# Voicecard-SVF-v05.net
KiCad netlist of a schematic drawn in EAGLE
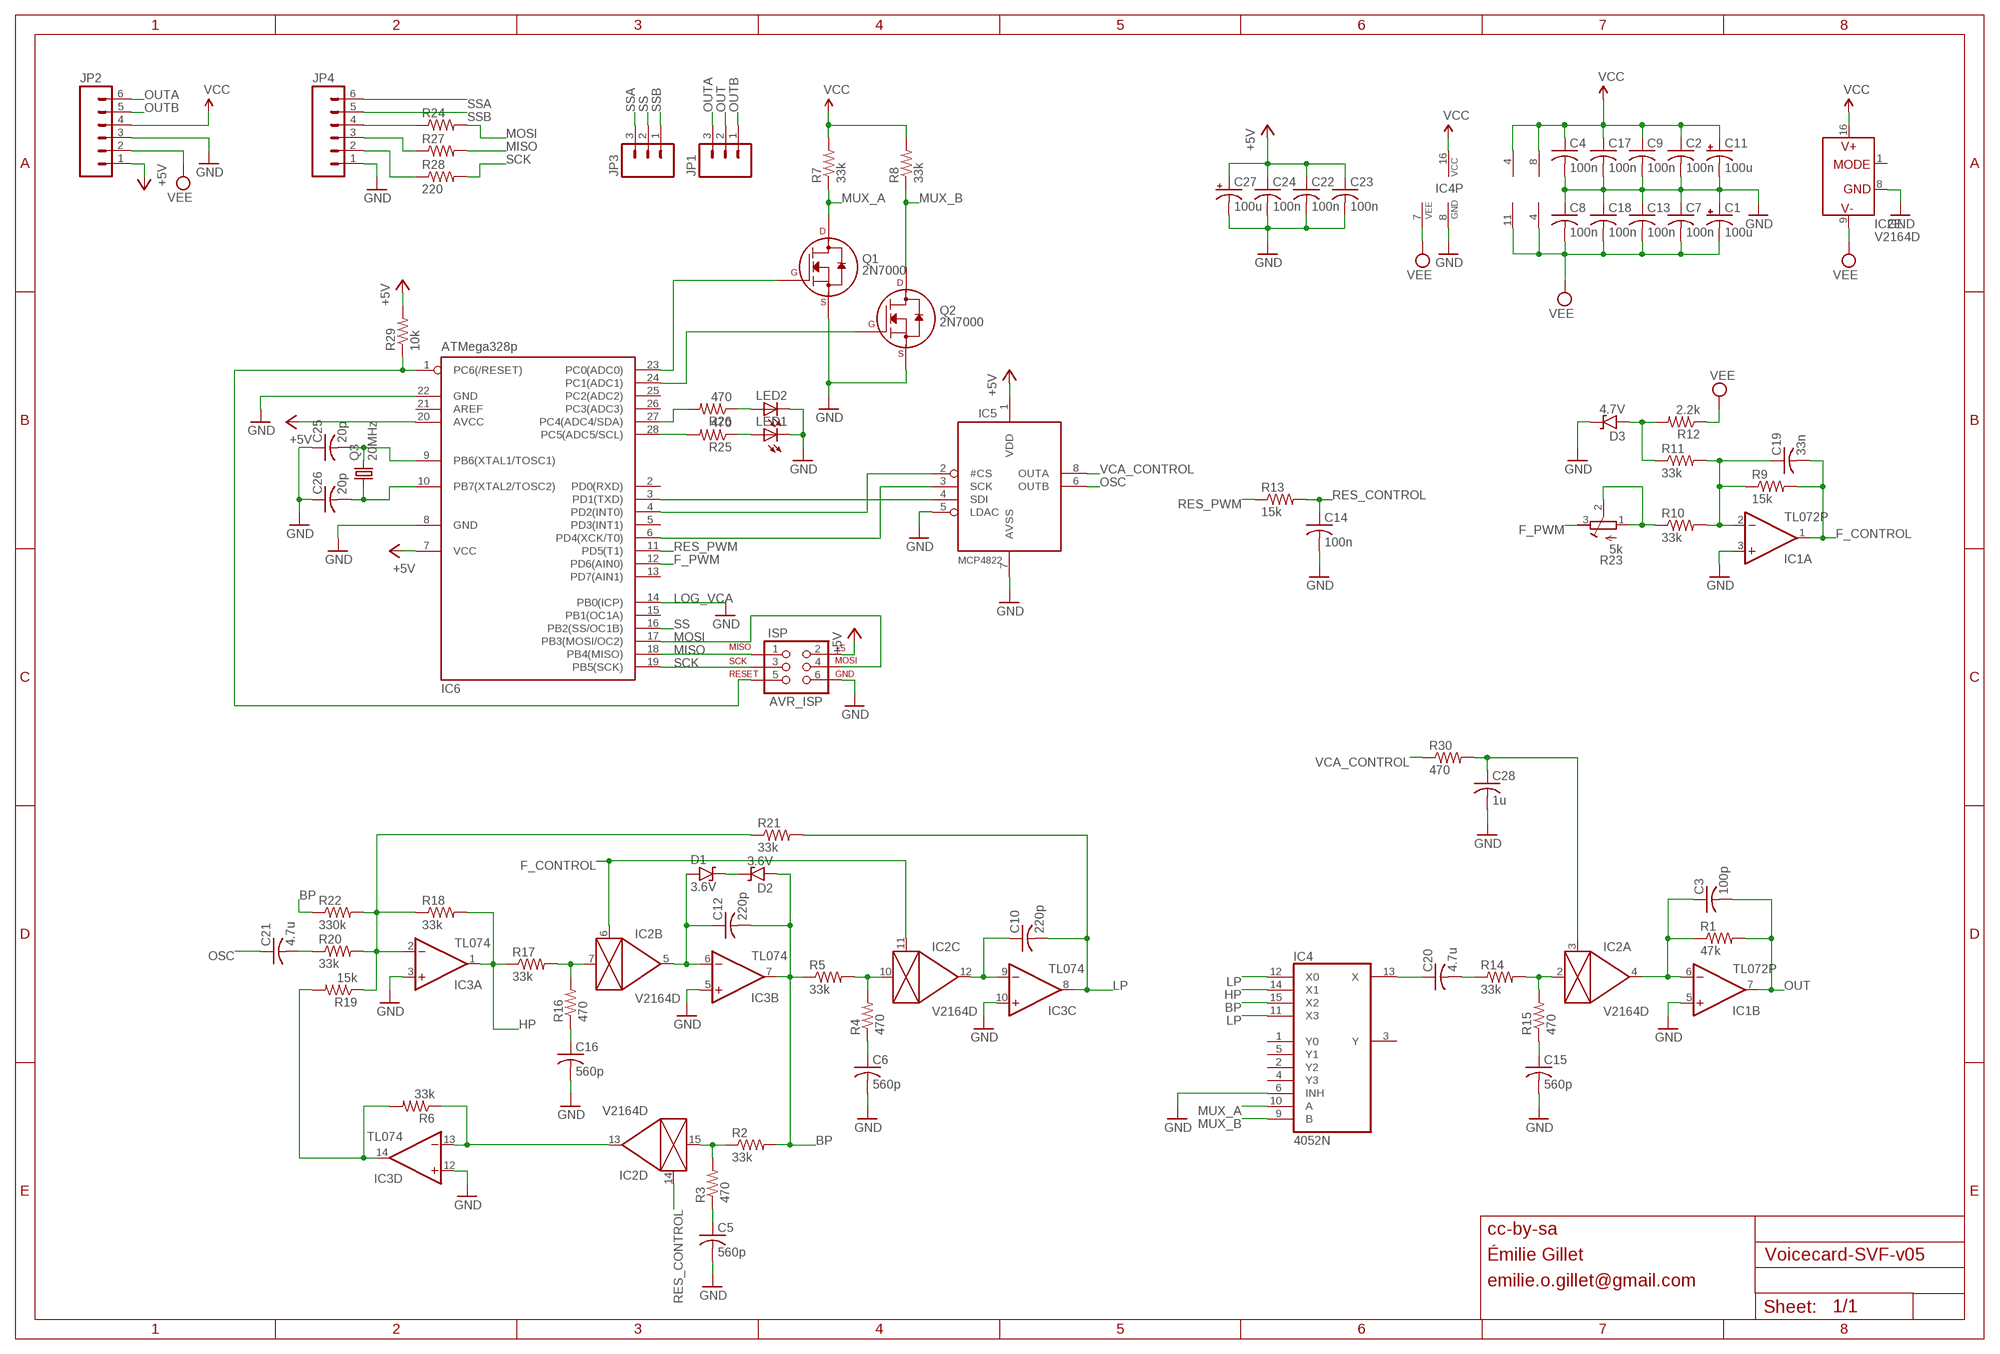
[diagram p0: schematic, sheet 1]

(export (version "E")
  (design (tool "Eeschema 10.0.6"))
  (components
    (comp (ref "C1")
      (value "100u")
      (footprint "eagle-import:E2,5-6")
      (libsource (lib "eagle-import") (part "CPOL-USE2.5-6"))
    )
    (comp (ref "C2")
      (value "100n")
      (footprint "eagle-import:C025-025X050")
      (libsource (lib "eagle-import") (part "C-US025-025X050"))
    )
    (comp (ref "C3")
      (value "100p")
      (footprint "eagle-import:C025-025X050")
      (libsource (lib "eagle-import") (part "C-US025-025X050"))
    )
    (comp (ref "C4")
      (value "100n")
      (footprint "eagle-import:C025-025X050")
      (libsource (lib "eagle-import") (part "C-US025-025X050"))
    )
    (comp (ref "C5")
      (value "560p")
      (footprint "eagle-import:C025-025X050")
      (libsource (lib "eagle-import") (part "C-US025-025X050"))
    )
    (comp (ref "C6")
      (value "560p")
      (footprint "eagle-import:C025-025X050")
      (libsource (lib "eagle-import") (part "C-US025-025X050"))
    )
    (comp (ref "C7")
      (value "100n")
      (footprint "eagle-import:C025-025X050")
      (libsource (lib "eagle-import") (part "C-US025-025X050"))
    )
    (comp (ref "C8")
      (value "100n")
      (footprint "eagle-import:C025-025X050")
      (libsource (lib "eagle-import") (part "C-US025-025X050"))
    )
    (comp (ref "C9")
      (value "100n")
      (footprint "eagle-import:C025-025X050")
      (libsource (lib "eagle-import") (part "C-US025-025X050"))
    )
    (comp (ref "C10")
      (value "220p")
      (footprint "eagle-import:C025-025X050")
      (libsource (lib "eagle-import") (part "C-US025-025X050"))
    )
    (comp (ref "C11")
      (value "100u")
      (footprint "eagle-import:E2,5-6")
      (libsource (lib "eagle-import") (part "CPOL-USE2.5-6"))
    )
    (comp (ref "C12")
      (value "220p")
      (footprint "eagle-import:C025-025X050")
      (libsource (lib "eagle-import") (part "C-US025-025X050"))
    )
    (comp (ref "C13")
      (value "100n")
      (footprint "eagle-import:C025-025X050")
      (libsource (lib "eagle-import") (part "C-US025-025X050"))
    )
    (comp (ref "C14")
      (value "100n")
      (footprint "eagle-import:C025-025X050")
      (libsource (lib "eagle-import") (part "C-US025-025X050"))
    )
    (comp (ref "C15")
      (value "560p")
      (footprint "eagle-import:C025-025X050")
      (libsource (lib "eagle-import") (part "C-US025-025X050"))
    )
    (comp (ref "C16")
      (value "560p")
      (footprint "eagle-import:C025-025X050")
      (libsource (lib "eagle-import") (part "C-US025-025X050"))
    )
    (comp (ref "C17")
      (value "100n")
      (footprint "eagle-import:C025-025X050")
      (libsource (lib "eagle-import") (part "C-US025-025X050"))
    )
    (comp (ref "C18")
      (value "100n")
      (footprint "eagle-import:C025-025X050")
      (libsource (lib "eagle-import") (part "C-US025-025X050"))
    )
    (comp (ref "C19")
      (value "33n")
      (footprint "eagle-import:C050-025X075")
      (libsource (lib "eagle-import") (part "C-US050-025X075"))
    )
    (comp (ref "C20")
      (value "4.7u")
      (footprint "eagle-import:ENP11-6.3")
      (libsource (lib "eagle-import") (part "C-US"))
    )
    (comp (ref "C21")
      (value "4.7u")
      (footprint "eagle-import:ENP11-6.3")
      (libsource (lib "eagle-import") (part "C-US"))
    )
    (comp (ref "C22")
      (value "100n")
      (footprint "eagle-import:C025-025X050")
      (libsource (lib "eagle-import") (part "C-US025-025X050"))
    )
    (comp (ref "C23")
      (value "100n")
      (footprint "eagle-import:C025-025X050")
      (libsource (lib "eagle-import") (part "C-US025-025X050"))
    )
    (comp (ref "C24")
      (value "100n")
      (footprint "eagle-import:C025-024X044")
      (libsource (lib "eagle-import") (part "C-US025-024X044"))
    )
    (comp (ref "C25")
      (value "20p")
      (footprint "eagle-import:C025-024X044")
      (libsource (lib "eagle-import") (part "C-US025-024X044"))
    )
    (comp (ref "C26")
      (value "20p")
      (footprint "eagle-import:C025-024X044")
      (libsource (lib "eagle-import") (part "C-US025-024X044"))
    )
    (comp (ref "C27")
      (value "100u")
      (footprint "eagle-import:E2,5-6")
      (libsource (lib "eagle-import") (part "CPOL-USE2.5-6"))
    )
    (comp (ref "C28")
      (value "1u")
      (footprint "eagle-import:C050-025X075")
      (libsource (lib "eagle-import") (part "C-US050-025X075"))
    )
    (comp (ref "D1")
      (value "3.6V")
      (footprint "eagle-import:D-5")
      (libsource (lib "eagle-import") (part "1N47XXDO35"))
    )
    (comp (ref "D2")
      (value "3.6V")
      (footprint "eagle-import:D-5")
      (libsource (lib "eagle-import") (part "1N47XXDO35"))
    )
    (comp (ref "D3")
      (value "4.7V")
      (footprint "eagle-import:D-5")
      (libsource (lib "eagle-import") (part "1N47XXDO35"))
    )
    (comp (ref "IC1")
      (value "TL072P")
      (footprint "eagle-import:DIL08")
      (libsource (lib "eagle-import") (part "TL072P"))
    )
    (comp (ref "IC2")
      (value "V2164D")
      (footprint "eagle-import:DIL16")
      (libsource (lib "eagle-import") (part "SSM2164P"))
    )
    (comp (ref "IC3")
      (value "TL074")
      (footprint "eagle-import:DIL14")
      (libsource (lib "eagle-import") (part "TL084P"))
    )
    (comp (ref "IC4")
      (value "4052N")
      (footprint "eagle-import:DIL16")
      (libsource (lib "eagle-import") (part "4052N"))
    )
    (comp (ref "IC5")
      (value "MCP4822")
      (footprint "eagle-import:DIL08")
      (libsource (lib "eagle-import") (part "MCP4822"))
    )
    (comp (ref "IC6")
      (value "ATMega328p")
      (footprint "eagle-import:DIL28-3")
      (libsource (lib "eagle-import") (part "MEGA8-P"))
    )
    (comp (ref "ISP")
      (value "AVR_ISP")
      (footprint "eagle-import:2X3")
      (libsource (lib "eagle-import") (part "AVR_SPI_PRG_6PTH"))
    )
    (comp (ref "JP1")
      (value "M03PTH")
      (footprint "eagle-import:1X03")
      (libsource (lib "eagle-import") (part "M03PTH"))
    )
    (comp (ref "JP2")
      (value "M06SIP")
      (footprint "eagle-import:1X06")
      (libsource (lib "eagle-import") (part "M06SIP"))
    )
    (comp (ref "JP3")
      (value "M03PTH")
      (footprint "eagle-import:1X03")
      (libsource (lib "eagle-import") (part "M03PTH"))
    )
    (comp (ref "JP4")
      (value "M06SIP")
      (footprint "eagle-import:1X06")
      (libsource (lib "eagle-import") (part "M06SIP"))
    )
    (comp (ref "LED1")
      (value "LED3MM")
      (footprint "eagle-import:LED3MM")
      (libsource (lib "eagle-import") (part "LED3MM"))
    )
    (comp (ref "LED2")
      (value "LED3MM")
      (footprint "eagle-import:LED3MM")
      (libsource (lib "eagle-import") (part "LED3MM"))
    )
    (comp (ref "Q1")
      (value "2N7000")
      (footprint "eagle-import:TO-92")
      (libsource (lib "eagle-import") (part "2N7000"))
    )
    (comp (ref "Q2")
      (value "2N7000")
      (footprint "eagle-import:TO-92")
      (libsource (lib "eagle-import") (part "2N7000"))
    )
    (comp (ref "Q3")
      (value "20MHz")
      (footprint "eagle-import:HC49U-V")
      (libsource (lib "eagle-import") (part "CRYSTALHC49U-V"))
    )
    (comp (ref "R1")
      (value "47k")
      (footprint "eagle-import:0204_7")
      (libsource (lib "eagle-import") (part "R-US_0204/7"))
    )
    (comp (ref "R2")
      (value "33k")
      (footprint "eagle-import:0204_7")
      (libsource (lib "eagle-import") (part "R-US_0204/7"))
    )
    (comp (ref "R3")
      (value "470")
      (footprint "eagle-import:0204_7")
      (libsource (lib "eagle-import") (part "R-US_0204/7"))
    )
    (comp (ref "R4")
      (value "470")
      (footprint "eagle-import:0204_7")
      (libsource (lib "eagle-import") (part "R-US_0204/7"))
    )
    (comp (ref "R5")
      (value "33k")
      (footprint "eagle-import:0204_7")
      (libsource (lib "eagle-import") (part "R-US_0204/7"))
    )
    (comp (ref "R6")
      (value "33k")
      (footprint "eagle-import:0204_7")
      (libsource (lib "eagle-import") (part "R-US_0204/7"))
    )
    (comp (ref "R7")
      (value "33k")
      (footprint "eagle-import:0204_7")
      (libsource (lib "eagle-import") (part "R-US_0204/7"))
    )
    (comp (ref "R8")
      (value "33k")
      (footprint "eagle-import:0204_7")
      (libsource (lib "eagle-import") (part "R-US_0204/7"))
    )
    (comp (ref "R9")
      (value "15k")
      (footprint "eagle-import:0204_7")
      (libsource (lib "eagle-import") (part "R-US_0204/7"))
    )
    (comp (ref "R10")
      (value "33k")
      (footprint "eagle-import:0204_7")
      (libsource (lib "eagle-import") (part "R-US_0204/7"))
    )
    (comp (ref "R11")
      (value "33k")
      (footprint "eagle-import:0204_7")
      (libsource (lib "eagle-import") (part "R-US_0204/7"))
    )
    (comp (ref "R12")
      (value "2.2k")
      (footprint "eagle-import:0204_7")
      (libsource (lib "eagle-import") (part "R-US_0204/7"))
    )
    (comp (ref "R13")
      (value "15k")
      (footprint "eagle-import:0204_7")
      (libsource (lib "eagle-import") (part "R-US_0204/7"))
    )
    (comp (ref "R14")
      (value "33k")
      (footprint "eagle-import:0204_7")
      (libsource (lib "eagle-import") (part "R-US_0204/7"))
    )
    (comp (ref "R15")
      (value "470")
      (footprint "eagle-import:0204_7")
      (libsource (lib "eagle-import") (part "R-US_0204/7"))
    )
    (comp (ref "R16")
      (value "470")
      (footprint "eagle-import:0204_7")
      (libsource (lib "eagle-import") (part "R-US_0204/7"))
    )
    (comp (ref "R17")
      (value "33k")
      (footprint "eagle-import:0204_7")
      (libsource (lib "eagle-import") (part "R-US_0204/7"))
    )
    (comp (ref "R18")
      (value "33k")
      (footprint "eagle-import:0204_7")
      (libsource (lib "eagle-import") (part "R-US_0204/7"))
    )
    (comp (ref "R19")
      (value "15k")
      (footprint "eagle-import:0204_7")
      (libsource (lib "eagle-import") (part "R-US_0204/7"))
    )
    (comp (ref "R20")
      (value "33k")
      (footprint "eagle-import:0204_7")
      (libsource (lib "eagle-import") (part "R-US_0204/7"))
    )
    (comp (ref "R21")
      (value "33k")
      (footprint "eagle-import:0204_7")
      (libsource (lib "eagle-import") (part "R-US_0204/7"))
    )
    (comp (ref "R22")
      (value "330k")
      (footprint "eagle-import:0204_7")
      (libsource (lib "eagle-import") (part "R-US_0204/7"))
    )
    (comp (ref "R23")
      (value "5k")
      (footprint "eagle-import:RTRIM3296P")
      (libsource (lib "eagle-import") (part "R-TRIMM3296P"))
    )
    (comp (ref "R24")
      (value "220")
      (footprint "eagle-import:0204_7")
      (libsource (lib "eagle-import") (part "R-US_0204/7"))
    )
    (comp (ref "R25")
      (value "470")
      (footprint "eagle-import:0204_7")
      (libsource (lib "eagle-import") (part "R-US_0204/7"))
    )
    (comp (ref "R26")
      (value "470")
      (footprint "eagle-import:0204_7")
      (libsource (lib "eagle-import") (part "R-US_0204/7"))
    )
    (comp (ref "R27")
      (value "220")
      (footprint "eagle-import:0204_7")
      (libsource (lib "eagle-import") (part "R-US_0204/7"))
    )
    (comp (ref "R28")
      (value "220")
      (footprint "eagle-import:0204_7")
      (libsource (lib "eagle-import") (part "R-US_0204/7"))
    )
    (comp (ref "R29")
      (value "10k")
      (footprint "eagle-import:0204_7")
      (libsource (lib "eagle-import") (part "R-US_0204/7"))
    )
    (comp (ref "R30")
      (value "470")
      (footprint "eagle-import:0204_7")
      (libsource (lib "eagle-import") (part "R-US_0204/7"))
    )
  )
  (nets
    (net (code "1") (name "+5V") (class "Default")
      (node (ref "C22") (pin "1") (pinfunction "1_1") (pintype "passive"))
      (node (ref "C23") (pin "1") (pinfunction "1_1") (pintype "passive"))
      (node (ref "C24") (pin "1") (pinfunction "1_1") (pintype "passive"))
      (node (ref "C27") (pin "+") (pinfunction "+_+") (pintype "passive"))
      (node (ref "IC5") (pin "1") (pinfunction "VDD_1") (pintype "power_in"))
      (node (ref "IC6") (pin "20") (pinfunction "AVCC_20") (pintype "power_in"))
      (node (ref "IC6") (pin "7") (pinfunction "VCC_7") (pintype "power_in"))
      (node (ref "ISP") (pin "2") (pinfunction "2_2") (pintype "passive"))
      (node (ref "JP2") (pin "1") (pinfunction "1_1") (pintype "passive"))
      (node (ref "R29") (pin "2") (pinfunction "2_2") (pintype "passive"))
    )
    (net (code "2") (name "/BP") (class "Default")
      (node (ref "C12") (pin "2") (pinfunction "2_2") (pintype "passive"))
      (node (ref "D2") (pin "A") (pinfunction "A_A") (pintype "passive"))
      (node (ref "IC3") (pin "7") (pinfunction "OUT_7") (pintype "output"))
      (node (ref "IC4") (pin "15") (pinfunction "X2_15") (pintype "bidirectional"))
      (node (ref "R2") (pin "2") (pinfunction "2_2") (pintype "passive"))
      (node (ref "R22") (pin "1") (pinfunction "1_1") (pintype "passive"))
      (node (ref "R5") (pin "1") (pinfunction "1_1") (pintype "passive"))
    )
    (net (code "3") (name "/F_CONTROL") (class "Default")
      (node (ref "C19") (pin "2") (pinfunction "2_2") (pintype "passive"))
      (node (ref "IC1") (pin "1") (pinfunction "OUT_1") (pintype "output"))
      (node (ref "IC2") (pin "11") (pinfunction "CTRL_11") (pintype "input"))
      (node (ref "IC2") (pin "6") (pinfunction "CTRL_6") (pintype "input"))
      (node (ref "R9") (pin "2") (pinfunction "2_2") (pintype "passive"))
    )
    (net (code "4") (name "/F_PWM") (class "Default")
      (node (ref "IC6") (pin "12") (pinfunction "PD6(AIN0)_12") (pintype "bidirectional"))
      (node (ref "R23") (pin "3") (pinfunction "A_3") (pintype "passive"))
    )
    (net (code "5") (name "/HP") (class "Default")
      (node (ref "IC3") (pin "1") (pinfunction "OUT_1") (pintype "output"))
      (node (ref "IC4") (pin "14") (pinfunction "X1_14") (pintype "bidirectional"))
      (node (ref "R17") (pin "1") (pinfunction "1_1") (pintype "passive"))
      (node (ref "R18") (pin "2") (pinfunction "2_2") (pintype "passive"))
    )
    (net (code "6") (name "/LP") (class "Default")
      (node (ref "C10") (pin "2") (pinfunction "2_2") (pintype "passive"))
      (node (ref "IC3") (pin "8") (pinfunction "OUT_8") (pintype "output"))
      (node (ref "IC4") (pin "11") (pinfunction "X3_11") (pintype "bidirectional"))
      (node (ref "IC4") (pin "12") (pinfunction "X0_12") (pintype "bidirectional"))
      (node (ref "R21") (pin "2") (pinfunction "2_2") (pintype "passive"))
    )
    (net (code "7") (name "/MISO") (class "Default")
      (node (ref "IC6") (pin "18") (pinfunction "PB4(MISO)_18") (pintype "bidirectional"))
      (node (ref "ISP") (pin "1") (pinfunction "1_1") (pintype "passive"))
      (node (ref "R27") (pin "2") (pinfunction "2_2") (pintype "passive"))
    )
    (net (code "8") (name "/MOSI") (class "Default")
      (node (ref "IC6") (pin "17") (pinfunction "PB3(MOSI/OC2)_17") (pintype "bidirectional"))
      (node (ref "ISP") (pin "4") (pinfunction "4_4") (pintype "passive"))
      (node (ref "R24") (pin "2") (pinfunction "2_2") (pintype "passive"))
    )
    (net (code "9") (name "/MUX_A") (class "Default")
      (node (ref "IC4") (pin "10") (pinfunction "A_10") (pintype "input"))
      (node (ref "Q1") (pin "3") (pinfunction "D_3") (pintype "bidirectional"))
      (node (ref "R7") (pin "1") (pinfunction "1_1") (pintype "passive"))
    )
    (net (code "10") (name "/MUX_B") (class "Default")
      (node (ref "IC4") (pin "9") (pinfunction "B_9") (pintype "input"))
      (node (ref "Q2") (pin "3") (pinfunction "D_3") (pintype "bidirectional"))
      (node (ref "R8") (pin "1") (pinfunction "1_1") (pintype "passive"))
    )
    (net (code "11") (name "/OSC") (class "Default")
      (node (ref "C21") (pin "+") (pinfunction "1_+") (pintype "passive"))
      (node (ref "IC5") (pin "6") (pinfunction "OUTB_6") (pintype "output"))
    )
    (net (code "12") (name "/OUT") (class "Default")
      (node (ref "C3") (pin "2") (pinfunction "2_2") (pintype "passive"))
      (node (ref "IC1") (pin "7") (pinfunction "OUT_7") (pintype "output"))
      (node (ref "JP1") (pin "2") (pinfunction "2_2") (pintype "passive"))
      (node (ref "R1") (pin "2") (pinfunction "2_2") (pintype "passive"))
    )
    (net (code "13") (name "/OUTA") (class "Default")
      (node (ref "JP1") (pin "3") (pinfunction "3_3") (pintype "passive"))
      (node (ref "JP2") (pin "6") (pinfunction "6_6") (pintype "passive"))
    )
    (net (code "14") (name "/OUTB") (class "Default")
      (node (ref "JP1") (pin "1") (pinfunction "1_1") (pintype "passive"))
      (node (ref "JP2") (pin "5") (pinfunction "5_5") (pintype "passive"))
    )
    (net (code "15") (name "/RES_CONTROL") (class "Default")
      (node (ref "C14") (pin "1") (pinfunction "1_1") (pintype "passive"))
      (node (ref "IC2") (pin "14") (pinfunction "CTRL_14") (pintype "input"))
      (node (ref "R13") (pin "2") (pinfunction "2_2") (pintype "passive"))
    )
    (net (code "16") (name "/RES_PWM") (class "Default")
      (node (ref "IC6") (pin "11") (pinfunction "PD5(T1)_11") (pintype "bidirectional"))
      (node (ref "R13") (pin "1") (pinfunction "1_1") (pintype "passive"))
    )
    (net (code "17") (name "/SCK") (class "Default")
      (node (ref "IC6") (pin "19") (pinfunction "PB5(SCK)_19") (pintype "bidirectional"))
      (node (ref "ISP") (pin "3") (pinfunction "3_3") (pintype "passive"))
      (node (ref "R28") (pin "2") (pinfunction "2_2") (pintype "passive"))
    )
    (net (code "18") (name "/SS") (class "Default")
      (node (ref "IC6") (pin "16") (pinfunction "PB2(SS/OC1B)_16") (pintype "bidirectional"))
      (node (ref "JP3") (pin "2") (pinfunction "2_2") (pintype "passive"))
    )
    (net (code "19") (name "/SSA") (class "Default")
      (node (ref "JP3") (pin "3") (pinfunction "3_3") (pintype "passive"))
      (node (ref "JP4") (pin "6") (pinfunction "6_6") (pintype "passive"))
    )
    (net (code "20") (name "/SSB") (class "Default")
      (node (ref "JP3") (pin "1") (pinfunction "1_1") (pintype "passive"))
      (node (ref "JP4") (pin "5") (pinfunction "5_5") (pintype "passive"))
    )
    (net (code "21") (name "/VCA_CONTROL") (class "Default")
      (node (ref "IC5") (pin "8") (pinfunction "OUTA_8") (pintype "output"))
      (node (ref "R30") (pin "1") (pinfunction "1_1") (pintype "passive"))
    )
    (net (code "22") (name "GND") (class "Default")
      (node (ref "C1") (pin "+") (pinfunction "+_+") (pintype "passive"))
      (node (ref "C11") (pin "-") (pinfunction "-_-") (pintype "passive"))
      (node (ref "C13") (pin "1") (pinfunction "1_1") (pintype "passive"))
      (node (ref "C14") (pin "2") (pinfunction "2_2") (pintype "passive"))
      (node (ref "C15") (pin "2") (pinfunction "2_2") (pintype "passive"))
      (node (ref "C16") (pin "2") (pinfunction "2_2") (pintype "passive"))
      (node (ref "C17") (pin "2") (pinfunction "2_2") (pintype "passive"))
      (node (ref "C18") (pin "1") (pinfunction "1_1") (pintype "passive"))
      (node (ref "C2") (pin "2") (pinfunction "2_2") (pintype "passive"))
      (node (ref "C22") (pin "2") (pinfunction "2_2") (pintype "passive"))
      (node (ref "C23") (pin "2") (pinfunction "2_2") (pintype "passive"))
      (node (ref "C24") (pin "2") (pinfunction "2_2") (pintype "passive"))
      (node (ref "C25") (pin "1") (pinfunction "1_1") (pintype "passive"))
      (node (ref "C26") (pin "1") (pinfunction "1_1") (pintype "passive"))
      (node (ref "C27") (pin "-") (pinfunction "-_-") (pintype "passive"))
      (node (ref "C28") (pin "2") (pinfunction "2_2") (pintype "passive"))
      (node (ref "C4") (pin "2") (pinfunction "2_2") (pintype "passive"))
      (node (ref "C5") (pin "2") (pinfunction "2_2") (pintype "passive"))
      (node (ref "C6") (pin "2") (pinfunction "2_2") (pintype "passive"))
      (node (ref "C7") (pin "1") (pinfunction "1_1") (pintype "passive"))
      (node (ref "C8") (pin "1") (pinfunction "1_1") (pintype "passive"))
      (node (ref "C9") (pin "2") (pinfunction "2_2") (pintype "passive"))
      (node (ref "D3") (pin "C") (pinfunction "C_C") (pintype "passive"))
      (node (ref "IC1") (pin "3") (pinfunction "+IN_3") (pintype "input"))
      (node (ref "IC1") (pin "5") (pinfunction "+IN_5") (pintype "input"))
      (node (ref "IC2") (pin "8") (pinfunction "GND_8") (pintype "power_in"))
      (node (ref "IC3") (pin "10") (pinfunction "+IN_10") (pintype "input"))
      (node (ref "IC3") (pin "12") (pinfunction "+IN_12") (pintype "input"))
      (node (ref "IC3") (pin "3") (pinfunction "+IN_3") (pintype "input"))
      (node (ref "IC3") (pin "5") (pinfunction "+IN_5") (pintype "input"))
      (node (ref "IC4") (pin "6") (pinfunction "INH_6") (pintype "input"))
      (node (ref "IC4") (pin "8") (pinfunction "GND_8") (pintype "power_in"))
      (node (ref "IC5") (pin "5") (pinfunction "LDAC_5") (pintype "input"))
      (node (ref "IC5") (pin "7") (pinfunction "AVSS_7") (pintype "power_in"))
      (node (ref "IC6") (pin "14") (pinfunction "PB0(ICP)_14") (pintype "bidirectional"))
      (node (ref "IC6") (pin "22") (pinfunction "GND_22") (pintype "power_in"))
      (node (ref "IC6") (pin "8") (pinfunction "GND_8") (pintype "power_in"))
      (node (ref "ISP") (pin "6") (pinfunction "6_6") (pintype "passive"))
      (node (ref "JP2") (pin "3") (pinfunction "3_3") (pintype "passive"))
      (node (ref "JP4") (pin "1") (pinfunction "1_1") (pintype "passive"))
      (node (ref "LED1") (pin "K") (pinfunction "C_K") (pintype "passive"))
      (node (ref "LED2") (pin "K") (pinfunction "C_K") (pintype "passive"))
      (node (ref "Q1") (pin "1") (pinfunction "S_1") (pintype "bidirectional"))
      (node (ref "Q2") (pin "1") (pinfunction "S_1") (pintype "bidirectional"))
    )
    (net (code "23") (name "Net-(C5-Pad1)") (class "Default")
      (node (ref "C5") (pin "1") (pinfunction "1_1") (pintype "passive"))
      (node (ref "R3") (pin "1") (pinfunction "1_1") (pintype "passive"))
    )
    (net (code "24") (name "Net-(C6-Pad1)") (class "Default")
      (node (ref "C6") (pin "1") (pinfunction "1_1") (pintype "passive"))
      (node (ref "R4") (pin "1") (pinfunction "1_1") (pintype "passive"))
    )
    (net (code "25") (name "Net-(C15-Pad1)") (class "Default")
      (node (ref "C15") (pin "1") (pinfunction "1_1") (pintype "passive"))
      (node (ref "R15") (pin "1") (pinfunction "1_1") (pintype "passive"))
    )
    (net (code "26") (name "Net-(C16-Pad1)") (class "Default")
      (node (ref "C16") (pin "1") (pinfunction "1_1") (pintype "passive"))
      (node (ref "R16") (pin "1") (pinfunction "1_1") (pintype "passive"))
    )
    (net (code "27") (name "Net-(C20-1)") (class "Default")
      (node (ref "C20") (pin "+") (pinfunction "1_+") (pintype "passive"))
      (node (ref "IC4") (pin "13") (pinfunction "X_13") (pintype "bidirectional"))
    )
    (net (code "28") (name "Net-(C20-2)") (class "Default")
      (node (ref "C20") (pin "-") (pinfunction "2_-") (pintype "passive"))
      (node (ref "R14") (pin "1") (pinfunction "1_1") (pintype "passive"))
    )
    (net (code "29") (name "Net-(C21-2)") (class "Default")
      (node (ref "C21") (pin "-") (pinfunction "2_-") (pintype "passive"))
      (node (ref "R20") (pin "1") (pinfunction "1_1") (pintype "passive"))
    )
    (net (code "30") (name "Net-(D1-PadC)") (class "Default")
      (node (ref "D1") (pin "C") (pinfunction "C_C") (pintype "passive"))
      (node (ref "D2") (pin "C") (pinfunction "C_C") (pintype "passive"))
    )
    (net (code "31") (name "Net-(D3-PadA)") (class "Default")
      (node (ref "D3") (pin "A") (pinfunction "A_A") (pintype "passive"))
      (node (ref "R11") (pin "1") (pinfunction "1_1") (pintype "passive"))
      (node (ref "R12") (pin "2") (pinfunction "2_2") (pintype "passive"))
    )
    (net (code "32") (name "Net-(IC1A--IN)") (class "Default")
      (node (ref "C19") (pin "1") (pinfunction "1_1") (pintype "passive"))
      (node (ref "IC1") (pin "2") (pinfunction "-IN_2") (pintype "input"))
      (node (ref "R10") (pin "2") (pinfunction "2_2") (pintype "passive"))
      (node (ref "R11") (pin "2") (pinfunction "2_2") (pintype "passive"))
      (node (ref "R9") (pin "1") (pinfunction "1_1") (pintype "passive"))
    )
    (net (code "33") (name "Net-(IC1B--IN)") (class "Default")
      (node (ref "C3") (pin "1") (pinfunction "1_1") (pintype "passive"))
      (node (ref "IC1") (pin "6") (pinfunction "-IN_6") (pintype "input"))
      (node (ref "IC2") (pin "4") (pinfunction "OUT_4") (pintype "output"))
      (node (ref "R1") (pin "1") (pinfunction "1_1") (pintype "passive"))
    )
    (net (code "34") (name "Net-(IC2A-CTRL)") (class "Default")
      (node (ref "C28") (pin "1") (pinfunction "1_1") (pintype "passive"))
      (node (ref "IC2") (pin "3") (pinfunction "CTRL_3") (pintype "input"))
      (node (ref "R30") (pin "2") (pinfunction "2_2") (pintype "passive"))
    )
    (net (code "35") (name "Net-(IC2A-IN)") (class "Default")
      (node (ref "IC2") (pin "2") (pinfunction "IN_2") (pintype "input"))
      (node (ref "R14") (pin "2") (pinfunction "2_2") (pintype "passive"))
      (node (ref "R15") (pin "2") (pinfunction "2_2") (pintype "passive"))
    )
    (net (code "36") (name "Net-(IC2B-IN)") (class "Default")
      (node (ref "IC2") (pin "7") (pinfunction "IN_7") (pintype "input"))
      (node (ref "R16") (pin "2") (pinfunction "2_2") (pintype "passive"))
      (node (ref "R17") (pin "2") (pinfunction "2_2") (pintype "passive"))
    )
    (net (code "37") (name "Net-(IC2B-OUT)") (class "Default")
      (node (ref "C12") (pin "1") (pinfunction "1_1") (pintype "passive"))
      (node (ref "D1") (pin "A") (pinfunction "A_A") (pintype "passive"))
      (node (ref "IC2") (pin "5") (pinfunction "OUT_5") (pintype "output"))
      (node (ref "IC3") (pin "6") (pinfunction "-IN_6") (pintype "input"))
    )
    (net (code "38") (name "Net-(IC2C-IN)") (class "Default")
      (node (ref "IC2") (pin "10") (pinfunction "IN_10") (pintype "input"))
      (node (ref "R4") (pin "2") (pinfunction "2_2") (pintype "passive"))
      (node (ref "R5") (pin "2") (pinfunction "2_2") (pintype "passive"))
    )
    (net (code "39") (name "Net-(IC2C-OUT)") (class "Default")
      (node (ref "C10") (pin "1") (pinfunction "1_1") (pintype "passive"))
      (node (ref "IC2") (pin "12") (pinfunction "OUT_12") (pintype "output"))
      (node (ref "IC3") (pin "9") (pinfunction "-IN_9") (pintype "input"))
    )
    (net (code "40") (name "Net-(IC2D-IN)") (class "Default")
      (node (ref "IC2") (pin "15") (pinfunction "IN_15") (pintype "input"))
      (node (ref "R2") (pin "1") (pinfunction "1_1") (pintype "passive"))
      (node (ref "R3") (pin "2") (pinfunction "2_2") (pintype "passive"))
    )
    (net (code "41") (name "Net-(IC2D-OUT)") (class "Default")
      (node (ref "IC2") (pin "13") (pinfunction "OUT_13") (pintype "output"))
      (node (ref "IC3") (pin "13") (pinfunction "-IN_13") (pintype "input"))
      (node (ref "R6") (pin "1") (pinfunction "1_1") (pintype "passive"))
    )
    (net (code "42") (name "Net-(IC3A--IN)") (class "Default")
      (node (ref "IC3") (pin "2") (pinfunction "-IN_2") (pintype "input"))
      (node (ref "R18") (pin "1") (pinfunction "1_1") (pintype "passive"))
      (node (ref "R19") (pin "1") (pinfunction "1_1") (pintype "passive"))
      (node (ref "R20") (pin "2") (pinfunction "2_2") (pintype "passive"))
      (node (ref "R21") (pin "1") (pinfunction "1_1") (pintype "passive"))
      (node (ref "R22") (pin "2") (pinfunction "2_2") (pintype "passive"))
    )
    (net (code "43") (name "Net-(IC3D-OUT)") (class "Default")
      (node (ref "IC3") (pin "14") (pinfunction "OUT_14") (pintype "output"))
      (node (ref "R19") (pin "2") (pinfunction "2_2") (pintype "passive"))
      (node (ref "R6") (pin "2") (pinfunction "2_2") (pintype "passive"))
    )
    (net (code "44") (name "Net-(IC5-#CS)") (class "Default")
      (node (ref "IC5") (pin "2") (pinfunction "#CS_2") (pintype "input"))
      (node (ref "IC6") (pin "4") (pinfunction "PD2(INT0)_4") (pintype "bidirectional"))
    )
    (net (code "45") (name "Net-(IC5-SCK)") (class "Default")
      (node (ref "IC5") (pin "3") (pinfunction "SCK_3") (pintype "input"))
      (node (ref "IC6") (pin "6") (pinfunction "PD4(XCK/T0)_6") (pintype "bidirectional"))
    )
    (net (code "46") (name "Net-(IC5-SDI)") (class "Default")
      (node (ref "IC5") (pin "4") (pinfunction "SDI_4") (pintype "input"))
      (node (ref "IC6") (pin "3") (pinfunction "PD1(TXD)_3") (pintype "bidirectional"))
    )
    (net (code "47") (name "Net-(IC6-PB6(XTAL1{slash}TOSC1))") (class "Default")
      (node (ref "C25") (pin "2") (pinfunction "2_2") (pintype "passive"))
      (node (ref "IC6") (pin "9") (pinfunction "PB6(XTAL1/TOSC1)_9") (pintype "bidirectional"))
      (node (ref "Q3") (pin "2") (pinfunction "2_2") (pintype "passive"))
    )
    (net (code "48") (name "Net-(IC6-PB7(XTAL2{slash}TOSC2))") (class "Default")
      (node (ref "C26") (pin "2") (pinfunction "2_2") (pintype "passive"))
      (node (ref "IC6") (pin "10") (pinfunction "PB7(XTAL2/TOSC2)_10") (pintype "bidirectional"))
      (node (ref "Q3") (pin "1") (pinfunction "1_1") (pintype "passive"))
    )
    (net (code "49") (name "Net-(IC6-PC0(ADC0))") (class "Default")
      (node (ref "IC6") (pin "23") (pinfunction "PC0(ADC0)_23") (pintype "bidirectional"))
      (node (ref "Q1") (pin "2") (pinfunction "G_2") (pintype "tri_state"))
    )
    (net (code "50") (name "Net-(IC6-PC1(ADC1))") (class "Default")
      (node (ref "IC6") (pin "24") (pinfunction "PC1(ADC1)_24") (pintype "bidirectional"))
      (node (ref "Q2") (pin "2") (pinfunction "G_2") (pintype "tri_state"))
    )
    (net (code "51") (name "Net-(IC6-PC4(ADC4{slash}SDA))") (class "Default")
      (node (ref "IC6") (pin "27") (pinfunction "PC4(ADC4/SDA)_27") (pintype "bidirectional"))
      (node (ref "R26") (pin "2") (pinfunction "2_2") (pintype "passive"))
    )
    (net (code "52") (name "Net-(IC6-PC5(ADC5{slash}SCL))") (class "Default")
      (node (ref "IC6") (pin "28") (pinfunction "PC5(ADC5/SCL)_28") (pintype "bidirectional"))
      (node (ref "R25") (pin "2") (pinfunction "2_2") (pintype "passive"))
    )
    (net (code "53") (name "Net-(IC6-PC6({slash}RESET))") (class "Default")
      (node (ref "IC6") (pin "1") (pinfunction "PC6(/RESET)_1") (pintype "bidirectional"))
      (node (ref "ISP") (pin "5") (pinfunction "5_5") (pintype "passive"))
      (node (ref "R29") (pin "1") (pinfunction "1_1") (pintype "passive"))
    )
    (net (code "54") (name "Net-(JP4-Pad2)") (class "Default")
      (node (ref "JP4") (pin "2") (pinfunction "2_2") (pintype "passive"))
      (node (ref "R28") (pin "1") (pinfunction "1_1") (pintype "passive"))
    )
    (net (code "55") (name "Net-(JP4-Pad3)") (class "Default")
      (node (ref "JP4") (pin "3") (pinfunction "3_3") (pintype "passive"))
      (node (ref "R27") (pin "1") (pinfunction "1_1") (pintype "passive"))
    )
    (net (code "56") (name "Net-(JP4-Pad4)") (class "Default")
      (node (ref "JP4") (pin "4") (pinfunction "4_4") (pintype "passive"))
      (node (ref "R24") (pin "1") (pinfunction "1_1") (pintype "passive"))
    )
    (net (code "57") (name "Net-(LED1-PadA)") (class "Default")
      (node (ref "LED1") (pin "A") (pinfunction "A_A") (pintype "passive"))
      (node (ref "R25") (pin "1") (pinfunction "1_1") (pintype "passive"))
    )
    (net (code "58") (name "Net-(LED2-PadA)") (class "Default")
      (node (ref "LED2") (pin "A") (pinfunction "A_A") (pintype "passive"))
      (node (ref "R26") (pin "1") (pinfunction "1_1") (pintype "passive"))
    )
    (net (code "59") (name "Net-(R23-E)") (class "Default")
      (node (ref "R10") (pin "1") (pinfunction "1_1") (pintype "passive"))
      (node (ref "R23") (pin "1") (pinfunction "E_1") (pintype "passive"))
      (node (ref "R23") (pin "2") (pinfunction "S_2") (pintype "passive"))
    )
    (net (code "60") (name "VCC") (class "Default")
      (node (ref "C11") (pin "+") (pinfunction "+_+") (pintype "passive"))
      (node (ref "C17") (pin "1") (pinfunction "1_1") (pintype "passive"))
      (node (ref "C2") (pin "1") (pinfunction "1_1") (pintype "passive"))
      (node (ref "C4") (pin "1") (pinfunction "1_1") (pintype "passive"))
      (node (ref "C9") (pin "1") (pinfunction "1_1") (pintype "passive"))
      (node (ref "IC1") (pin "8") (pinfunction "V+_8") (pintype "power_in"))
      (node (ref "IC2") (pin "16") (pinfunction "V+_16") (pintype "power_in"))
      (node (ref "IC3") (pin "4") (pinfunction "V+_4") (pintype "power_in"))
      (node (ref "IC4") (pin "16") (pinfunction "VCC_16") (pintype "power_in"))
      (node (ref "JP2") (pin "4") (pinfunction "4_4") (pintype "passive"))
      (node (ref "R7") (pin "2") (pinfunction "2_2") (pintype "passive"))
      (node (ref "R8") (pin "2") (pinfunction "2_2") (pintype "passive"))
    )
    (net (code "61") (name "VEE") (class "Default")
      (node (ref "C1") (pin "-") (pinfunction "-_-") (pintype "passive"))
      (node (ref "C13") (pin "2") (pinfunction "2_2") (pintype "passive"))
      (node (ref "C18") (pin "2") (pinfunction "2_2") (pintype "passive"))
      (node (ref "C7") (pin "2") (pinfunction "2_2") (pintype "passive"))
      (node (ref "C8") (pin "2") (pinfunction "2_2") (pintype "passive"))
      (node (ref "IC1") (pin "4") (pinfunction "V-_4") (pintype "power_in"))
      (node (ref "IC2") (pin "9") (pinfunction "V-_9") (pintype "power_in"))
      (node (ref "IC3") (pin "11") (pinfunction "V-_11") (pintype "power_in"))
      (node (ref "IC4") (pin "7") (pinfunction "VEE_7") (pintype "power_in"))
      (node (ref "JP2") (pin "2") (pinfunction "2_2") (pintype "passive"))
      (node (ref "R12") (pin "1") (pinfunction "1_1") (pintype "passive"))
    )
    (net (code "62") (name "unconnected-(IC2E-MODE-Pad1)") (class "Default")
      (node (ref "IC2") (pin "1") (pinfunction "MODE_1") (pintype "input"))
    )
    (net (code "63") (name "unconnected-(IC4A-Y-Pad3)") (class "Default")
      (node (ref "IC4") (pin "3") (pinfunction "Y_3") (pintype "bidirectional"))
    )
    (net (code "64") (name "unconnected-(IC4A-Y0-Pad1)") (class "Default")
      (node (ref "IC4") (pin "1") (pinfunction "Y0_1") (pintype "bidirectional"))
    )
    (net (code "65") (name "unconnected-(IC4A-Y1-Pad5)") (class "Default")
      (node (ref "IC4") (pin "5") (pinfunction "Y1_5") (pintype "bidirectional"))
    )
    (net (code "66") (name "unconnected-(IC4A-Y2-Pad2)") (class "Default")
      (node (ref "IC4") (pin "2") (pinfunction "Y2_2") (pintype "bidirectional"))
    )
    (net (code "67") (name "unconnected-(IC4A-Y3-Pad4)") (class "Default")
      (node (ref "IC4") (pin "4") (pinfunction "Y3_4") (pintype "bidirectional"))
    )
    (net (code "68") (name "unconnected-(IC6-AREF-Pad21)") (class "Default")
      (node (ref "IC6") (pin "21") (pinfunction "AREF_21") (pintype "passive"))
    )
    (net (code "69") (name "unconnected-(IC6-PB1(OC1A)-Pad15)") (class "Default")
      (node (ref "IC6") (pin "15") (pinfunction "PB1(OC1A)_15") (pintype "bidirectional"))
    )
    (net (code "70") (name "unconnected-(IC6-PC2(ADC2)-Pad25)") (class "Default")
      (node (ref "IC6") (pin "25") (pinfunction "PC2(ADC2)_25") (pintype "bidirectional"))
    )
    (net (code "71") (name "unconnected-(IC6-PC3(ADC3)-Pad26)") (class "Default")
      (node (ref "IC6") (pin "26") (pinfunction "PC3(ADC3)_26") (pintype "bidirectional"))
    )
    (net (code "72") (name "unconnected-(IC6-PD0(RXD)-Pad2)") (class "Default")
      (node (ref "IC6") (pin "2") (pinfunction "PD0(RXD)_2") (pintype "bidirectional"))
    )
    (net (code "73") (name "unconnected-(IC6-PD3(INT1)-Pad5)") (class "Default")
      (node (ref "IC6") (pin "5") (pinfunction "PD3(INT1)_5") (pintype "bidirectional"))
    )
    (net (code "74") (name "unconnected-(IC6-PD7(AIN1)-Pad13)") (class "Default")
      (node (ref "IC6") (pin "13") (pinfunction "PD7(AIN1)_13") (pintype "bidirectional"))
    )
  )
)
